# rgb_strip_x5.net
KiCad netlist of a schematic drawn in EAGLE
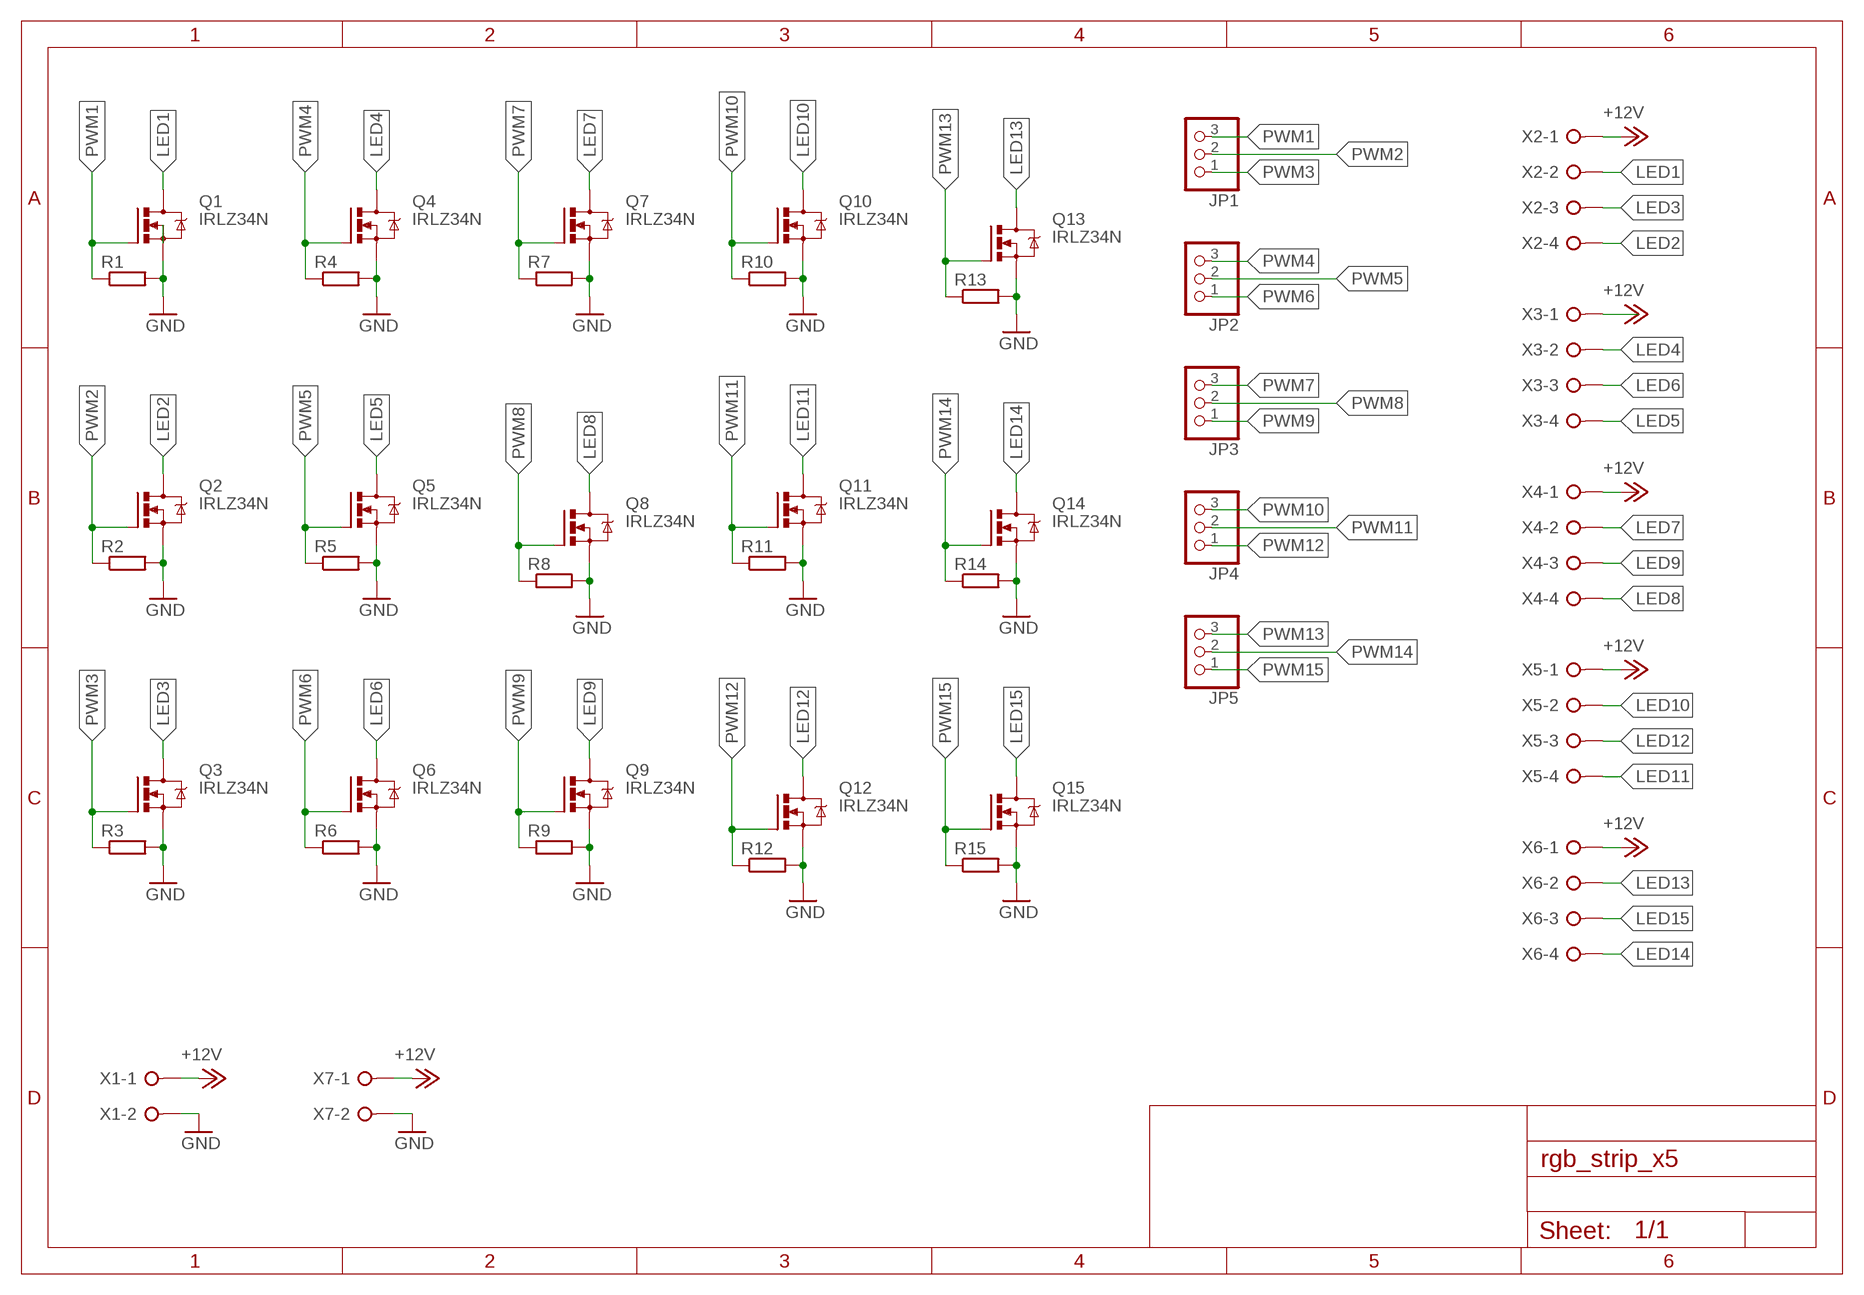
[diagram p0: schematic, sheet 1]

(export (version "E")
  (design (tool "Eeschema 10.0.6"))
  (components
    (comp (ref "JP1")
      (value "PINHD-1X3")
      (footprint "eagle-import:1X03")
      (libsource (lib "eagle-import") (part "PINHD-1X3"))
    )
    (comp (ref "JP2")
      (value "PINHD-1X3")
      (footprint "eagle-import:1X03")
      (libsource (lib "eagle-import") (part "PINHD-1X3"))
    )
    (comp (ref "JP3")
      (value "PINHD-1X3")
      (footprint "eagle-import:1X03")
      (libsource (lib "eagle-import") (part "PINHD-1X3"))
    )
    (comp (ref "JP4")
      (value "PINHD-1X3")
      (footprint "eagle-import:1X03")
      (libsource (lib "eagle-import") (part "PINHD-1X3"))
    )
    (comp (ref "JP5")
      (value "PINHD-1X3")
      (footprint "eagle-import:1X03")
      (libsource (lib "eagle-import") (part "PINHD-1X3"))
    )
    (comp (ref "Q1")
      (value "IRLZ34N")
      (footprint "eagle-import:TO220BV")
      (libsource (lib "eagle-import") (part "IRLZ44ZTO220BV"))
    )
    (comp (ref "Q2")
      (value "IRLZ34N")
      (footprint "eagle-import:TO220BV")
      (libsource (lib "eagle-import") (part "IRLZ44ZTO220BV"))
    )
    (comp (ref "Q3")
      (value "IRLZ34N")
      (footprint "eagle-import:TO220BV")
      (libsource (lib "eagle-import") (part "IRLZ44ZTO220BV"))
    )
    (comp (ref "Q4")
      (value "IRLZ34N")
      (footprint "eagle-import:TO220BV")
      (libsource (lib "eagle-import") (part "IRLZ44ZTO220BV"))
    )
    (comp (ref "Q5")
      (value "IRLZ34N")
      (footprint "eagle-import:TO220BV")
      (libsource (lib "eagle-import") (part "IRLZ44ZTO220BV"))
    )
    (comp (ref "Q6")
      (value "IRLZ34N")
      (footprint "eagle-import:TO220BV")
      (libsource (lib "eagle-import") (part "IRLZ44ZTO220BV"))
    )
    (comp (ref "Q7")
      (value "IRLZ34N")
      (footprint "eagle-import:TO220BV")
      (libsource (lib "eagle-import") (part "IRLZ44ZTO220BV"))
    )
    (comp (ref "Q8")
      (value "IRLZ34N")
      (footprint "eagle-import:TO220BV")
      (libsource (lib "eagle-import") (part "IRLZ44ZTO220BV"))
    )
    (comp (ref "Q9")
      (value "IRLZ34N")
      (footprint "eagle-import:TO220BV")
      (libsource (lib "eagle-import") (part "IRLZ44ZTO220BV"))
    )
    (comp (ref "Q10")
      (value "IRLZ34N")
      (footprint "eagle-import:TO220BV")
      (libsource (lib "eagle-import") (part "IRLZ44ZTO220BV"))
    )
    (comp (ref "Q11")
      (value "IRLZ34N")
      (footprint "eagle-import:TO220BV")
      (libsource (lib "eagle-import") (part "IRLZ44ZTO220BV"))
    )
    (comp (ref "Q12")
      (value "IRLZ34N")
      (footprint "eagle-import:TO220BV")
      (libsource (lib "eagle-import") (part "IRLZ44ZTO220BV"))
    )
    (comp (ref "Q13")
      (value "IRLZ34N")
      (footprint "eagle-import:TO220BV")
      (libsource (lib "eagle-import") (part "IRLZ44ZTO220BV"))
    )
    (comp (ref "Q14")
      (value "IRLZ34N")
      (footprint "eagle-import:TO220BV")
      (libsource (lib "eagle-import") (part "IRLZ44ZTO220BV"))
    )
    (comp (ref "Q15")
      (value "IRLZ34N")
      (footprint "eagle-import:TO220BV")
      (libsource (lib "eagle-import") (part "IRLZ44ZTO220BV"))
    )
    (comp (ref "R1")
      (value "R-EU_0207/10")
      (footprint "eagle-import:0207_10")
      (libsource (lib "eagle-import") (part "R-EU_0207/10"))
    )
    (comp (ref "R2")
      (value "R-EU_0207/10")
      (footprint "eagle-import:0207_10")
      (libsource (lib "eagle-import") (part "R-EU_0207/10"))
    )
    (comp (ref "R3")
      (value "R-EU_0207/10")
      (footprint "eagle-import:0207_10")
      (libsource (lib "eagle-import") (part "R-EU_0207/10"))
    )
    (comp (ref "R4")
      (value "R-EU_0207/10")
      (footprint "eagle-import:0207_10")
      (libsource (lib "eagle-import") (part "R-EU_0207/10"))
    )
    (comp (ref "R5")
      (value "R-EU_0207/10")
      (footprint "eagle-import:0207_10")
      (libsource (lib "eagle-import") (part "R-EU_0207/10"))
    )
    (comp (ref "R6")
      (value "R-EU_0207/10")
      (footprint "eagle-import:0207_10")
      (libsource (lib "eagle-import") (part "R-EU_0207/10"))
    )
    (comp (ref "R7")
      (value "R-EU_0207/10")
      (footprint "eagle-import:0207_10")
      (libsource (lib "eagle-import") (part "R-EU_0207/10"))
    )
    (comp (ref "R8")
      (value "R-EU_0207/10")
      (footprint "eagle-import:0207_10")
      (libsource (lib "eagle-import") (part "R-EU_0207/10"))
    )
    (comp (ref "R9")
      (value "R-EU_0207/10")
      (footprint "eagle-import:0207_10")
      (libsource (lib "eagle-import") (part "R-EU_0207/10"))
    )
    (comp (ref "R10")
      (value "R-EU_0207/10")
      (footprint "eagle-import:0207_10")
      (libsource (lib "eagle-import") (part "R-EU_0207/10"))
    )
    (comp (ref "R11")
      (value "R-EU_0207/10")
      (footprint "eagle-import:0207_10")
      (libsource (lib "eagle-import") (part "R-EU_0207/10"))
    )
    (comp (ref "R12")
      (value "R-EU_0207/10")
      (footprint "eagle-import:0207_10")
      (libsource (lib "eagle-import") (part "R-EU_0207/10"))
    )
    (comp (ref "R13")
      (value "R-EU_0207/10")
      (footprint "eagle-import:0207_10")
      (libsource (lib "eagle-import") (part "R-EU_0207/10"))
    )
    (comp (ref "R14")
      (value "R-EU_0207/10")
      (footprint "eagle-import:0207_10")
      (libsource (lib "eagle-import") (part "R-EU_0207/10"))
    )
    (comp (ref "R15")
      (value "R-EU_0207/10")
      (footprint "eagle-import:0207_10")
      (libsource (lib "eagle-import") (part "R-EU_0207/10"))
    )
    (comp (ref "X1")
      (value "W237-02P")
      (footprint "eagle-import:W237-132")
      (libsource (lib "eagle-import") (part "W237-02P"))
    )
    (comp (ref "X2")
      (value "W237-04P")
      (footprint "eagle-import:W237-4P")
      (libsource (lib "eagle-import") (part "W237-04P"))
    )
    (comp (ref "X3")
      (value "W237-04P")
      (footprint "eagle-import:W237-4P")
      (libsource (lib "eagle-import") (part "W237-04P"))
    )
    (comp (ref "X4")
      (value "W237-04P")
      (footprint "eagle-import:W237-4P")
      (libsource (lib "eagle-import") (part "W237-04P"))
    )
    (comp (ref "X5")
      (value "W237-04P")
      (footprint "eagle-import:W237-4P")
      (libsource (lib "eagle-import") (part "W237-04P"))
    )
    (comp (ref "X6")
      (value "W237-04P")
      (footprint "eagle-import:W237-4P")
      (libsource (lib "eagle-import") (part "W237-04P"))
    )
    (comp (ref "X7")
      (value "W237-02P")
      (footprint "eagle-import:W237-132")
      (libsource (lib "eagle-import") (part "W237-02P"))
    )
  )
  (nets
    (net (code "1") (name "+12V") (class "Default")
      (node (ref "X1") (pin "1") (pinfunction "KL_1") (pintype "passive"))
      (node (ref "X2") (pin "1") (pinfunction "KL_1") (pintype "passive"))
      (node (ref "X3") (pin "1") (pinfunction "KL_1") (pintype "passive"))
      (node (ref "X4") (pin "1") (pinfunction "KL_1") (pintype "passive"))
      (node (ref "X5") (pin "1") (pinfunction "KL_1") (pintype "passive"))
      (node (ref "X6") (pin "1") (pinfunction "KL_1") (pintype "passive"))
      (node (ref "X7") (pin "1") (pinfunction "KL_1") (pintype "passive"))
    )
    (net (code "2") (name "GND") (class "Default")
      (node (ref "Q1") (pin "S") (pinfunction "S_S") (pintype "passive"))
      (node (ref "Q10") (pin "S") (pinfunction "S_S") (pintype "passive"))
      (node (ref "Q11") (pin "S") (pinfunction "S_S") (pintype "passive"))
      (node (ref "Q12") (pin "S") (pinfunction "S_S") (pintype "passive"))
      (node (ref "Q13") (pin "S") (pinfunction "S_S") (pintype "passive"))
      (node (ref "Q14") (pin "S") (pinfunction "S_S") (pintype "passive"))
      (node (ref "Q15") (pin "S") (pinfunction "S_S") (pintype "passive"))
      (node (ref "Q2") (pin "S") (pinfunction "S_S") (pintype "passive"))
      (node (ref "Q3") (pin "S") (pinfunction "S_S") (pintype "passive"))
      (node (ref "Q4") (pin "S") (pinfunction "S_S") (pintype "passive"))
      (node (ref "Q5") (pin "S") (pinfunction "S_S") (pintype "passive"))
      (node (ref "Q6") (pin "S") (pinfunction "S_S") (pintype "passive"))
      (node (ref "Q7") (pin "S") (pinfunction "S_S") (pintype "passive"))
      (node (ref "Q8") (pin "S") (pinfunction "S_S") (pintype "passive"))
      (node (ref "Q9") (pin "S") (pinfunction "S_S") (pintype "passive"))
      (node (ref "R1") (pin "2") (pinfunction "2_2") (pintype "passive"))
      (node (ref "R10") (pin "2") (pinfunction "2_2") (pintype "passive"))
      (node (ref "R11") (pin "2") (pinfunction "2_2") (pintype "passive"))
      (node (ref "R12") (pin "2") (pinfunction "2_2") (pintype "passive"))
      (node (ref "R13") (pin "2") (pinfunction "2_2") (pintype "passive"))
      (node (ref "R14") (pin "2") (pinfunction "2_2") (pintype "passive"))
      (node (ref "R15") (pin "2") (pinfunction "2_2") (pintype "passive"))
      (node (ref "R2") (pin "2") (pinfunction "2_2") (pintype "passive"))
      (node (ref "R3") (pin "2") (pinfunction "2_2") (pintype "passive"))
      (node (ref "R4") (pin "2") (pinfunction "2_2") (pintype "passive"))
      (node (ref "R5") (pin "2") (pinfunction "2_2") (pintype "passive"))
      (node (ref "R6") (pin "2") (pinfunction "2_2") (pintype "passive"))
      (node (ref "R7") (pin "2") (pinfunction "2_2") (pintype "passive"))
      (node (ref "R8") (pin "2") (pinfunction "2_2") (pintype "passive"))
      (node (ref "R9") (pin "2") (pinfunction "2_2") (pintype "passive"))
      (node (ref "X1") (pin "2") (pinfunction "KL_2") (pintype "passive"))
      (node (ref "X7") (pin "2") (pinfunction "KL_2") (pintype "passive"))
    )
    (net (code "3") (name "LED1") (class "Default")
      (node (ref "Q1") (pin "D") (pinfunction "D_D") (pintype "passive"))
      (node (ref "X2") (pin "2") (pinfunction "KL_2") (pintype "passive"))
    )
    (net (code "4") (name "LED2") (class "Default")
      (node (ref "Q2") (pin "D") (pinfunction "D_D") (pintype "passive"))
      (node (ref "X2") (pin "4") (pinfunction "KL_4") (pintype "passive"))
    )
    (net (code "5") (name "LED3") (class "Default")
      (node (ref "Q3") (pin "D") (pinfunction "D_D") (pintype "passive"))
      (node (ref "X2") (pin "3") (pinfunction "KL_3") (pintype "passive"))
    )
    (net (code "6") (name "LED4") (class "Default")
      (node (ref "Q4") (pin "D") (pinfunction "D_D") (pintype "passive"))
      (node (ref "X3") (pin "2") (pinfunction "KL_2") (pintype "passive"))
    )
    (net (code "7") (name "LED5") (class "Default")
      (node (ref "Q5") (pin "D") (pinfunction "D_D") (pintype "passive"))
      (node (ref "X3") (pin "4") (pinfunction "KL_4") (pintype "passive"))
    )
    (net (code "8") (name "LED6") (class "Default")
      (node (ref "Q6") (pin "D") (pinfunction "D_D") (pintype "passive"))
      (node (ref "X3") (pin "3") (pinfunction "KL_3") (pintype "passive"))
    )
    (net (code "9") (name "LED7") (class "Default")
      (node (ref "Q7") (pin "D") (pinfunction "D_D") (pintype "passive"))
      (node (ref "X4") (pin "2") (pinfunction "KL_2") (pintype "passive"))
    )
    (net (code "10") (name "LED8") (class "Default")
      (node (ref "Q8") (pin "D") (pinfunction "D_D") (pintype "passive"))
      (node (ref "X4") (pin "4") (pinfunction "KL_4") (pintype "passive"))
    )
    (net (code "11") (name "LED9") (class "Default")
      (node (ref "Q9") (pin "D") (pinfunction "D_D") (pintype "passive"))
      (node (ref "X4") (pin "3") (pinfunction "KL_3") (pintype "passive"))
    )
    (net (code "12") (name "LED10") (class "Default")
      (node (ref "Q10") (pin "D") (pinfunction "D_D") (pintype "passive"))
      (node (ref "X5") (pin "2") (pinfunction "KL_2") (pintype "passive"))
    )
    (net (code "13") (name "LED11") (class "Default")
      (node (ref "Q11") (pin "D") (pinfunction "D_D") (pintype "passive"))
      (node (ref "X5") (pin "4") (pinfunction "KL_4") (pintype "passive"))
    )
    (net (code "14") (name "LED12") (class "Default")
      (node (ref "Q12") (pin "D") (pinfunction "D_D") (pintype "passive"))
      (node (ref "X5") (pin "3") (pinfunction "KL_3") (pintype "passive"))
    )
    (net (code "15") (name "LED13") (class "Default")
      (node (ref "Q13") (pin "D") (pinfunction "D_D") (pintype "passive"))
      (node (ref "X6") (pin "2") (pinfunction "KL_2") (pintype "passive"))
    )
    (net (code "16") (name "LED14") (class "Default")
      (node (ref "Q14") (pin "D") (pinfunction "D_D") (pintype "passive"))
      (node (ref "X6") (pin "4") (pinfunction "KL_4") (pintype "passive"))
    )
    (net (code "17") (name "LED15") (class "Default")
      (node (ref "Q15") (pin "D") (pinfunction "D_D") (pintype "passive"))
      (node (ref "X6") (pin "3") (pinfunction "KL_3") (pintype "passive"))
    )
    (net (code "18") (name "PWM1") (class "Default")
      (node (ref "JP1") (pin "3") (pinfunction "3_3") (pintype "passive"))
      (node (ref "Q1") (pin "G") (pinfunction "G_G") (pintype "passive"))
      (node (ref "R1") (pin "1") (pinfunction "1_1") (pintype "passive"))
    )
    (net (code "19") (name "PWM2") (class "Default")
      (node (ref "JP1") (pin "2") (pinfunction "2_2") (pintype "passive"))
      (node (ref "Q2") (pin "G") (pinfunction "G_G") (pintype "passive"))
      (node (ref "R2") (pin "1") (pinfunction "1_1") (pintype "passive"))
    )
    (net (code "20") (name "PWM3") (class "Default")
      (node (ref "JP1") (pin "1") (pinfunction "1_1") (pintype "passive"))
      (node (ref "Q3") (pin "G") (pinfunction "G_G") (pintype "passive"))
      (node (ref "R3") (pin "1") (pinfunction "1_1") (pintype "passive"))
    )
    (net (code "21") (name "PWM4") (class "Default")
      (node (ref "JP2") (pin "3") (pinfunction "3_3") (pintype "passive"))
      (node (ref "Q4") (pin "G") (pinfunction "G_G") (pintype "passive"))
      (node (ref "R4") (pin "1") (pinfunction "1_1") (pintype "passive"))
    )
    (net (code "22") (name "PWM5") (class "Default")
      (node (ref "JP2") (pin "2") (pinfunction "2_2") (pintype "passive"))
      (node (ref "Q5") (pin "G") (pinfunction "G_G") (pintype "passive"))
      (node (ref "R5") (pin "1") (pinfunction "1_1") (pintype "passive"))
    )
    (net (code "23") (name "PWM6") (class "Default")
      (node (ref "JP2") (pin "1") (pinfunction "1_1") (pintype "passive"))
      (node (ref "Q6") (pin "G") (pinfunction "G_G") (pintype "passive"))
      (node (ref "R6") (pin "1") (pinfunction "1_1") (pintype "passive"))
    )
    (net (code "24") (name "PWM7") (class "Default")
      (node (ref "JP3") (pin "3") (pinfunction "3_3") (pintype "passive"))
      (node (ref "Q7") (pin "G") (pinfunction "G_G") (pintype "passive"))
      (node (ref "R7") (pin "1") (pinfunction "1_1") (pintype "passive"))
    )
    (net (code "25") (name "PWM8") (class "Default")
      (node (ref "JP3") (pin "2") (pinfunction "2_2") (pintype "passive"))
      (node (ref "Q8") (pin "G") (pinfunction "G_G") (pintype "passive"))
      (node (ref "R8") (pin "1") (pinfunction "1_1") (pintype "passive"))
    )
    (net (code "26") (name "PWM9") (class "Default")
      (node (ref "JP3") (pin "1") (pinfunction "1_1") (pintype "passive"))
      (node (ref "Q9") (pin "G") (pinfunction "G_G") (pintype "passive"))
      (node (ref "R9") (pin "1") (pinfunction "1_1") (pintype "passive"))
    )
    (net (code "27") (name "PWM10") (class "Default")
      (node (ref "JP4") (pin "3") (pinfunction "3_3") (pintype "passive"))
      (node (ref "Q10") (pin "G") (pinfunction "G_G") (pintype "passive"))
      (node (ref "R10") (pin "1") (pinfunction "1_1") (pintype "passive"))
    )
    (net (code "28") (name "PWM11") (class "Default")
      (node (ref "JP4") (pin "2") (pinfunction "2_2") (pintype "passive"))
      (node (ref "Q11") (pin "G") (pinfunction "G_G") (pintype "passive"))
      (node (ref "R11") (pin "1") (pinfunction "1_1") (pintype "passive"))
    )
    (net (code "29") (name "PWM12") (class "Default")
      (node (ref "JP4") (pin "1") (pinfunction "1_1") (pintype "passive"))
      (node (ref "Q12") (pin "G") (pinfunction "G_G") (pintype "passive"))
      (node (ref "R12") (pin "1") (pinfunction "1_1") (pintype "passive"))
    )
    (net (code "30") (name "PWM13") (class "Default")
      (node (ref "JP5") (pin "3") (pinfunction "3_3") (pintype "passive"))
      (node (ref "Q13") (pin "G") (pinfunction "G_G") (pintype "passive"))
      (node (ref "R13") (pin "1") (pinfunction "1_1") (pintype "passive"))
    )
    (net (code "31") (name "PWM14") (class "Default")
      (node (ref "JP5") (pin "2") (pinfunction "2_2") (pintype "passive"))
      (node (ref "Q14") (pin "G") (pinfunction "G_G") (pintype "passive"))
      (node (ref "R14") (pin "1") (pinfunction "1_1") (pintype "passive"))
    )
    (net (code "32") (name "PWM15") (class "Default")
      (node (ref "JP5") (pin "1") (pinfunction "1_1") (pintype "passive"))
      (node (ref "Q15") (pin "G") (pinfunction "G_G") (pintype "passive"))
      (node (ref "R15") (pin "1") (pinfunction "1_1") (pintype "passive"))
    )
  )
)
